# ResolverBoard.net
KiCad netlist of a schematic drawn in EAGLE
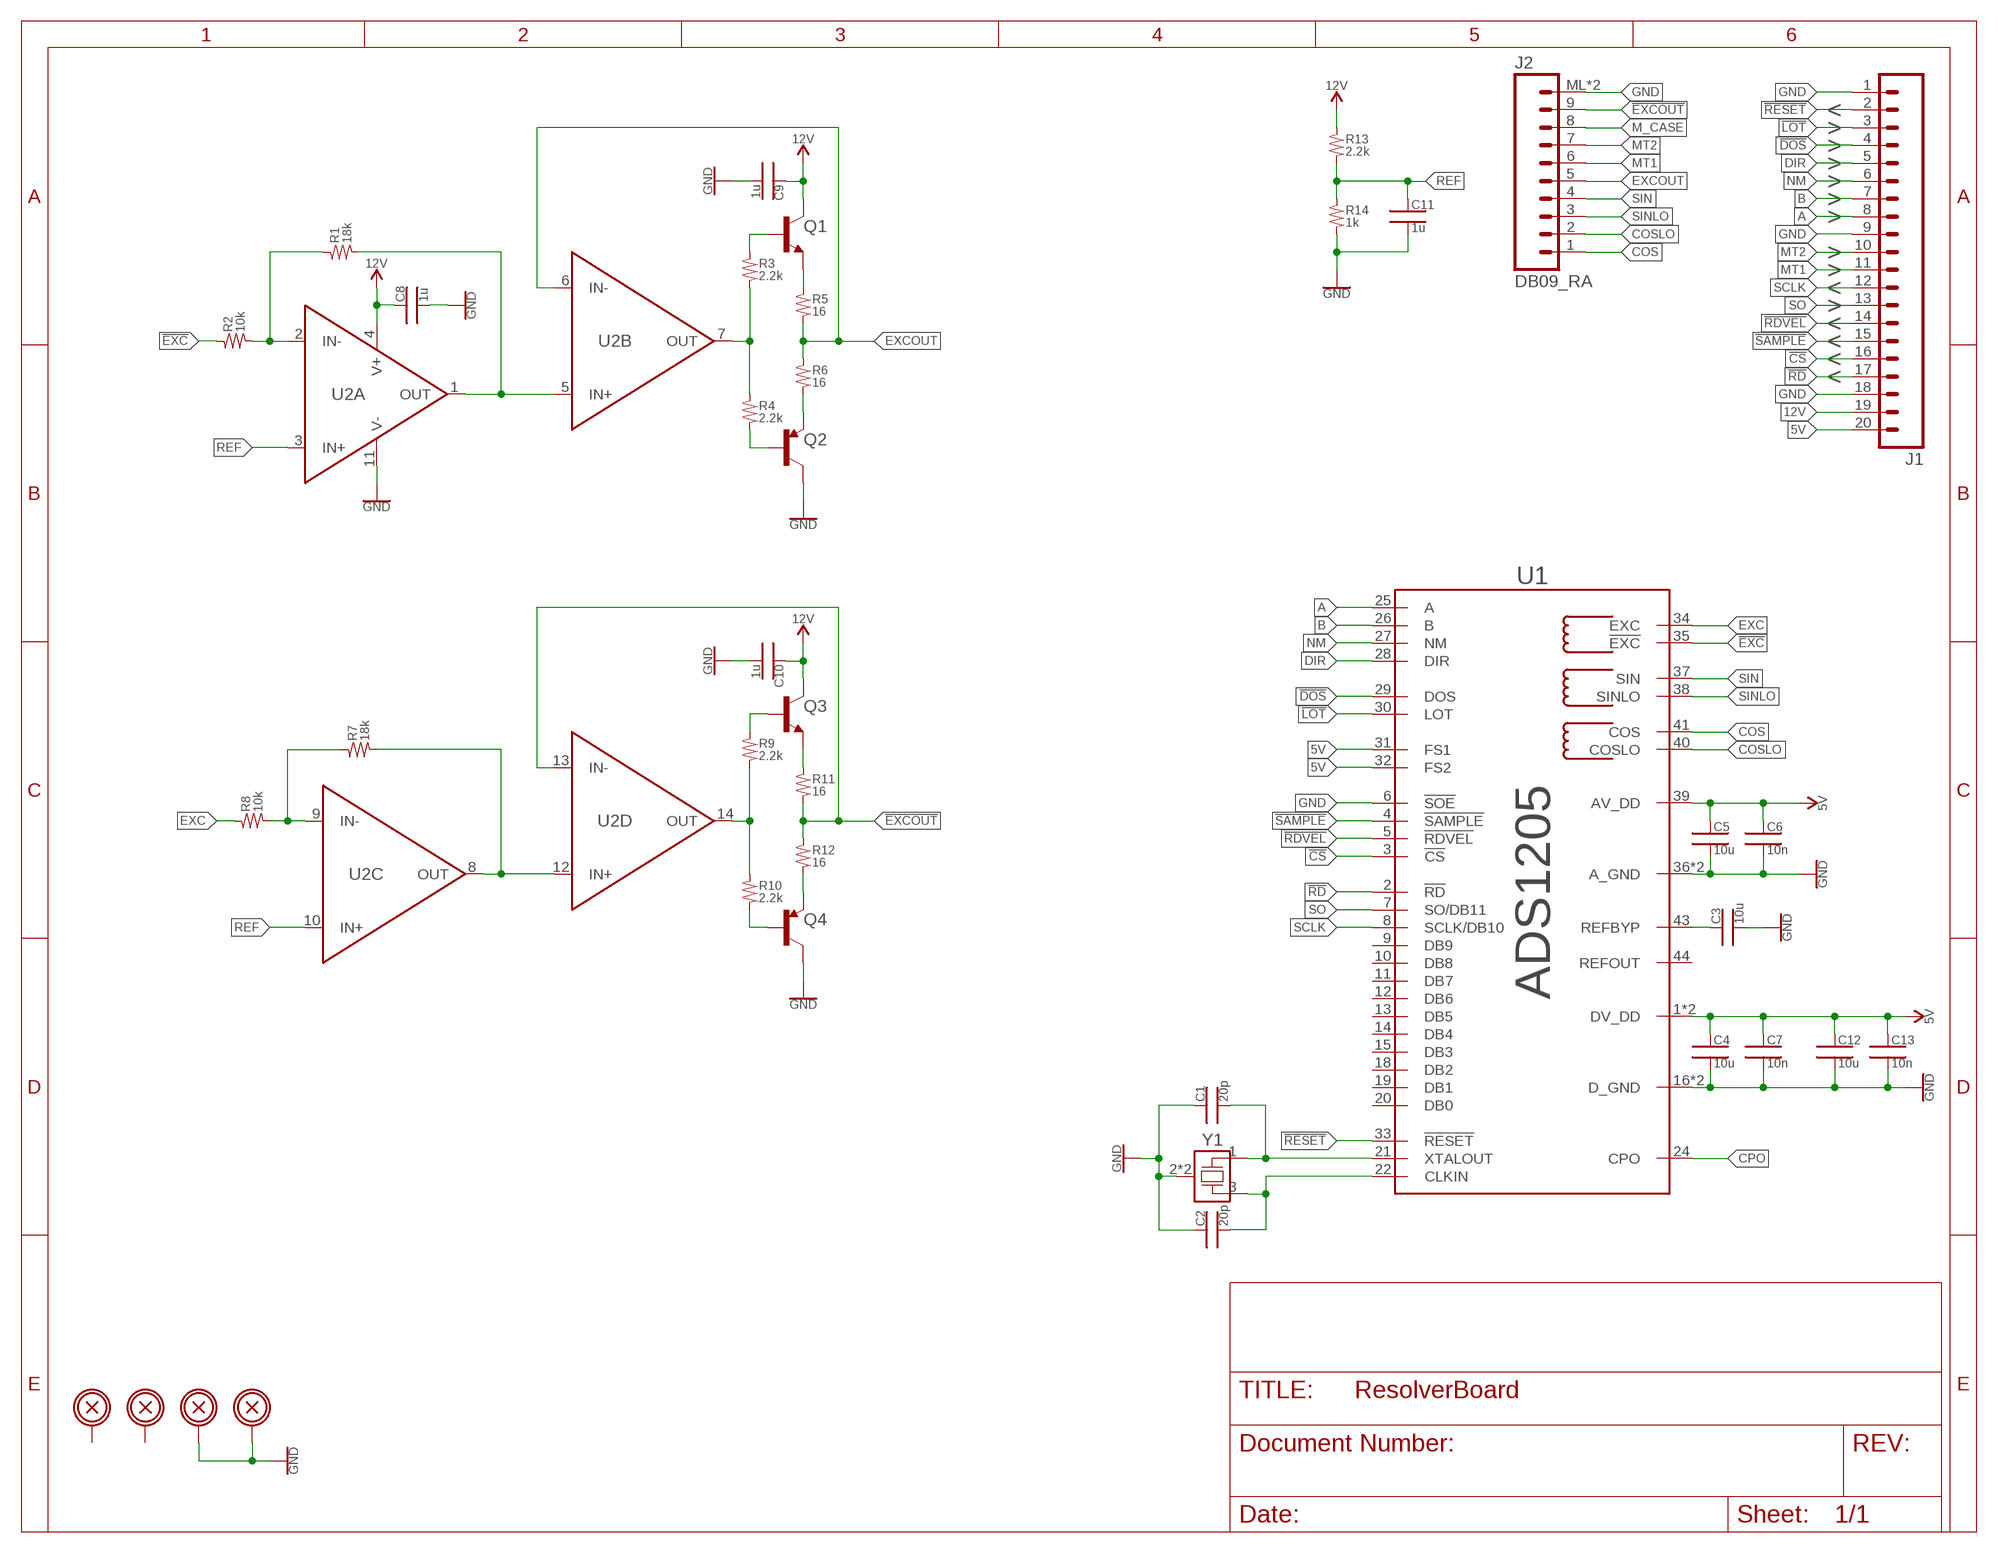
[diagram p0: schematic, sheet 1]

(export (version "E")
  (design (tool "Eeschema 10.0.6"))
  (components
    (comp (ref "C1")
      (value "20p")
      (footprint "eagle-import:0402")
      (libsource (lib "eagle-import") (part "CAP_SMD_0402"))
    )
    (comp (ref "C2")
      (value "20p")
      (footprint "eagle-import:0402")
      (libsource (lib "eagle-import") (part "CAP_SMD_0402"))
    )
    (comp (ref "C3")
      (value "10u")
      (footprint "eagle-import:0603")
      (libsource (lib "eagle-import") (part "CAP_SMD_0603"))
    )
    (comp (ref "C4")
      (value "10u")
      (footprint "eagle-import:0603")
      (libsource (lib "eagle-import") (part "CAP_SMD_0603"))
    )
    (comp (ref "C5")
      (value "10u")
      (footprint "eagle-import:0603")
      (libsource (lib "eagle-import") (part "CAP_SMD_0603"))
    )
    (comp (ref "C6")
      (value "10n")
      (footprint "eagle-import:0402")
      (libsource (lib "eagle-import") (part "CAP_SMD_0402"))
    )
    (comp (ref "C7")
      (value "10n")
      (footprint "eagle-import:0402")
      (libsource (lib "eagle-import") (part "CAP_SMD_0402"))
    )
    (comp (ref "C8")
      (value "1u")
      (footprint "eagle-import:0402")
      (libsource (lib "eagle-import") (part "CAP_SMD_0402"))
    )
    (comp (ref "C9")
      (value "1u")
      (footprint "eagle-import:0402")
      (libsource (lib "eagle-import") (part "CAP_SMD_0402"))
    )
    (comp (ref "C10")
      (value "1u")
      (footprint "eagle-import:0402")
      (libsource (lib "eagle-import") (part "CAP_SMD_0402"))
    )
    (comp (ref "C11")
      (value "1u")
      (footprint "eagle-import:0402")
      (libsource (lib "eagle-import") (part "CAP_SMD_0402"))
    )
    (comp (ref "C12")
      (value "10u")
      (footprint "eagle-import:0603")
      (libsource (lib "eagle-import") (part "CAP_SMD_0603"))
    )
    (comp (ref "C13")
      (value "10n")
      (footprint "eagle-import:0402")
      (libsource (lib "eagle-import") (part "CAP_SMD_0402"))
    )
    (comp (ref "H1")
      (value "BOLTHOLE_M3")
      (footprint "eagle-import:M3_HOLE")
      (libsource (lib "eagle-import") (part "BOLTHOLE_M3"))
    )
    (comp (ref "H2")
      (value "BOLTHOLE_M3")
      (footprint "eagle-import:M3_HOLE")
      (libsource (lib "eagle-import") (part "BOLTHOLE_M3"))
    )
    (comp (ref "H3")
      (value "BOLTHOLE_M3")
      (footprint "eagle-import:M3_HOLE")
      (libsource (lib "eagle-import") (part "BOLTHOLE_M3"))
    )
    (comp (ref "H4")
      (value "BOLTHOLE_M3")
      (footprint "eagle-import:M3_HOLE")
      (libsource (lib "eagle-import") (part "BOLTHOLE_M3"))
    )
    (comp (ref "J1")
      (value "M20")
      (footprint "eagle-import:1X20")
      (libsource (lib "eagle-import") (part "M20"))
    )
    (comp (ref "J2")
      (value "DB09_RA")
      (footprint "eagle-import:AE10921")
      (libsource (lib "eagle-import") (part "DB09_RA"))
    )
    (comp (ref "Q1")
      (value "BJT_NPN")
      (footprint "eagle-import:SOT23-3")
      (libsource (lib "eagle-import") (part "BJT_NPN"))
    )
    (comp (ref "Q2")
      (value "BJT_PNP")
      (footprint "eagle-import:SOT23-3")
      (libsource (lib "eagle-import") (part "BJT_PNP"))
    )
    (comp (ref "Q3")
      (value "BJT_NPN")
      (footprint "eagle-import:SOT23-3")
      (libsource (lib "eagle-import") (part "BJT_NPN"))
    )
    (comp (ref "Q4")
      (value "BJT_PNP")
      (footprint "eagle-import:SOT23-3")
      (libsource (lib "eagle-import") (part "BJT_PNP"))
    )
    (comp (ref "R1")
      (value "18k")
      (footprint "eagle-import:0402")
      (libsource (lib "eagle-import") (part "RES_SMD_0402"))
    )
    (comp (ref "R2")
      (value "10k")
      (footprint "eagle-import:0402")
      (libsource (lib "eagle-import") (part "RES_SMD_0402"))
    )
    (comp (ref "R3")
      (value "2.2k")
      (footprint "eagle-import:0402")
      (libsource (lib "eagle-import") (part "RES_SMD_0402"))
    )
    (comp (ref "R4")
      (value "2.2k")
      (footprint "eagle-import:0402")
      (libsource (lib "eagle-import") (part "RES_SMD_0402"))
    )
    (comp (ref "R5")
      (value "16")
      (footprint "eagle-import:0805")
      (libsource (lib "eagle-import") (part "RES_SMD_0805"))
    )
    (comp (ref "R6")
      (value "16")
      (footprint "eagle-import:0805")
      (libsource (lib "eagle-import") (part "RES_SMD_0805"))
    )
    (comp (ref "R7")
      (value "18k")
      (footprint "eagle-import:0402")
      (libsource (lib "eagle-import") (part "RES_SMD_0402"))
    )
    (comp (ref "R8")
      (value "10k")
      (footprint "eagle-import:0402")
      (libsource (lib "eagle-import") (part "RES_SMD_0402"))
    )
    (comp (ref "R9")
      (value "2.2k")
      (footprint "eagle-import:0402")
      (libsource (lib "eagle-import") (part "RES_SMD_0402"))
    )
    (comp (ref "R10")
      (value "2.2k")
      (footprint "eagle-import:0402")
      (libsource (lib "eagle-import") (part "RES_SMD_0402"))
    )
    (comp (ref "R11")
      (value "16")
      (footprint "eagle-import:0805")
      (libsource (lib "eagle-import") (part "RES_SMD_0805"))
    )
    (comp (ref "R12")
      (value "16")
      (footprint "eagle-import:0805")
      (libsource (lib "eagle-import") (part "RES_SMD_0805"))
    )
    (comp (ref "R13")
      (value "2.2k")
      (footprint "eagle-import:0402")
      (libsource (lib "eagle-import") (part "RES_SMD_0402"))
    )
    (comp (ref "R14")
      (value "1k")
      (footprint "eagle-import:0402")
      (libsource (lib "eagle-import") (part "RES_SMD_0402"))
    )
    (comp (ref "U1")
      (value "ADS1205")
      (footprint "eagle-import:LQFP44")
      (libsource (lib "eagle-import") (part "ADS1205"))
    )
    (comp (ref "U2")
      (value "OPA4171D")
      (footprint "eagle-import:SOIC_14")
      (libsource (lib "eagle-import") (part "OPA4171D"))
    )
    (comp (ref "Y1")
      (value "LFXTAL061486")
      (footprint "eagle-import:5X3.2MM_SMD_XTAL")
      (libsource (lib "eagle-import") (part "LFXTAL061486"))
    )
  )
  (nets
    (net (code "1") (name "/~{CS}") (class "Default")
      (node (ref "J1") (pin "16") (pinfunction "16_16") (pintype "passive"))
      (node (ref "U1") (pin "3") (pinfunction "~{CS}_3") (pintype "bidirectional"))
    )
    (net (code "2") (name "/~{DOS}") (class "Default")
      (node (ref "J1") (pin "4") (pinfunction "4_4") (pintype "passive"))
      (node (ref "U1") (pin "29") (pinfunction "DOS_29") (pintype "bidirectional"))
    )
    (net (code "3") (name "/~{EXCOUT}") (class "Default")
      (node (ref "J2") (pin "9") (pinfunction "9_9") (pintype "passive"))
      (node (ref "R11") (pin "2") (pinfunction "2_2") (pintype "passive"))
      (node (ref "R12") (pin "1") (pinfunction "1_1") (pintype "passive"))
      (node (ref "U2") (pin "13") (pinfunction "IN-_13") (pintype "bidirectional"))
    )
    (net (code "4") (name "/~{EXC}") (class "Default")
      (node (ref "R2") (pin "1") (pinfunction "1_1") (pintype "passive"))
      (node (ref "U1") (pin "35") (pinfunction "~{EXC}_35") (pintype "bidirectional"))
    )
    (net (code "5") (name "/~{LOT}") (class "Default")
      (node (ref "J1") (pin "3") (pinfunction "3_3") (pintype "passive"))
      (node (ref "U1") (pin "30") (pinfunction "LOT_30") (pintype "bidirectional"))
    )
    (net (code "6") (name "/~{RDVEL}") (class "Default")
      (node (ref "J1") (pin "14") (pinfunction "14_14") (pintype "passive"))
      (node (ref "U1") (pin "5") (pinfunction "~{RDVEL}_5") (pintype "bidirectional"))
    )
    (net (code "7") (name "/~{RD}") (class "Default")
      (node (ref "J1") (pin "17") (pinfunction "17_17") (pintype "passive"))
      (node (ref "U1") (pin "2") (pinfunction "~{RD}_2") (pintype "bidirectional"))
    )
    (net (code "8") (name "/~{RESET}") (class "Default")
      (node (ref "J1") (pin "2") (pinfunction "2_2") (pintype "passive"))
      (node (ref "U1") (pin "33") (pinfunction "~{RESET}_33") (pintype "bidirectional"))
    )
    (net (code "9") (name "/~{SAMPLE}") (class "Default")
      (node (ref "J1") (pin "15") (pinfunction "15_15") (pintype "passive"))
      (node (ref "U1") (pin "4") (pinfunction "~{SAMPLE}_4") (pintype "bidirectional"))
    )
    (net (code "10") (name "5V") (class "Default")
      (node (ref "C12") (pin "1") (pinfunction "1_1") (pintype "passive"))
      (node (ref "C13") (pin "1") (pinfunction "1_1") (pintype "passive"))
      (node (ref "C4") (pin "1") (pinfunction "1_1") (pintype "passive"))
      (node (ref "C5") (pin "1") (pinfunction "1_1") (pintype "passive"))
      (node (ref "C6") (pin "1") (pinfunction "1_1") (pintype "passive"))
      (node (ref "C7") (pin "1") (pinfunction "1_1") (pintype "passive"))
      (node (ref "J1") (pin "20") (pinfunction "20_20") (pintype "passive"))
      (node (ref "U1") (pin "1") (pinfunction "DV_DD_1") (pintype "bidirectional"))
      (node (ref "U1") (pin "17") (pinfunction "DV_DD_17") (pintype "bidirectional"))
      (node (ref "U1") (pin "31") (pinfunction "FS1_31") (pintype "bidirectional"))
      (node (ref "U1") (pin "32") (pinfunction "FS2_32") (pintype "bidirectional"))
      (node (ref "U1") (pin "39") (pinfunction "AV_DD_39") (pintype "bidirectional"))
    )
    (net (code "11") (name "12V") (class "Default")
      (node (ref "C10") (pin "1") (pinfunction "1_1") (pintype "passive"))
      (node (ref "C8") (pin "1") (pinfunction "1_1") (pintype "passive"))
      (node (ref "C9") (pin "1") (pinfunction "1_1") (pintype "passive"))
      (node (ref "J1") (pin "19") (pinfunction "19_19") (pintype "passive"))
      (node (ref "Q1") (pin "3") (pinfunction "C_3") (pintype "passive"))
      (node (ref "Q3") (pin "3") (pinfunction "C_3") (pintype "passive"))
      (node (ref "R13") (pin "1") (pinfunction "1_1") (pintype "passive"))
      (node (ref "U2") (pin "4") (pinfunction "V+_4") (pintype "bidirectional"))
    )
    (net (code "12") (name "A") (class "Default")
      (node (ref "J1") (pin "8") (pinfunction "8_8") (pintype "passive"))
      (node (ref "U1") (pin "25") (pinfunction "A_25") (pintype "bidirectional"))
    )
    (net (code "13") (name "B") (class "Default")
      (node (ref "J1") (pin "7") (pinfunction "7_7") (pintype "passive"))
      (node (ref "U1") (pin "26") (pinfunction "B_26") (pintype "bidirectional"))
    )
    (net (code "14") (name "COS") (class "Default")
      (node (ref "J2") (pin "1") (pinfunction "1_1") (pintype "passive"))
      (node (ref "U1") (pin "41") (pinfunction "COS_41") (pintype "bidirectional"))
    )
    (net (code "15") (name "COSLO") (class "Default")
      (node (ref "J2") (pin "2") (pinfunction "2_2") (pintype "passive"))
      (node (ref "U1") (pin "40") (pinfunction "COSLO_40") (pintype "bidirectional"))
    )
    (net (code "16") (name "CPO") (class "Default")
      (node (ref "U1") (pin "24") (pinfunction "CPO_24") (pintype "bidirectional"))
    )
    (net (code "17") (name "DIR") (class "Default")
      (node (ref "J1") (pin "5") (pinfunction "5_5") (pintype "passive"))
      (node (ref "U1") (pin "28") (pinfunction "DIR_28") (pintype "bidirectional"))
    )
    (net (code "18") (name "EXC") (class "Default")
      (node (ref "R8") (pin "1") (pinfunction "1_1") (pintype "passive"))
      (node (ref "U1") (pin "34") (pinfunction "EXC_34") (pintype "bidirectional"))
    )
    (net (code "19") (name "EXCOUT") (class "Default")
      (node (ref "J2") (pin "5") (pinfunction "5_5") (pintype "passive"))
      (node (ref "R5") (pin "2") (pinfunction "2_2") (pintype "passive"))
      (node (ref "R6") (pin "1") (pinfunction "1_1") (pintype "passive"))
      (node (ref "U2") (pin "6") (pinfunction "IN-_6") (pintype "bidirectional"))
    )
    (net (code "20") (name "GND") (class "Default")
      (node (ref "C1") (pin "1") (pinfunction "1_1") (pintype "passive"))
      (node (ref "C10") (pin "2") (pinfunction "2_2") (pintype "passive"))
      (node (ref "C11") (pin "2") (pinfunction "2_2") (pintype "passive"))
      (node (ref "C12") (pin "2") (pinfunction "2_2") (pintype "passive"))
      (node (ref "C13") (pin "2") (pinfunction "2_2") (pintype "passive"))
      (node (ref "C2") (pin "1") (pinfunction "1_1") (pintype "passive"))
      (node (ref "C3") (pin "2") (pinfunction "2_2") (pintype "passive"))
      (node (ref "C4") (pin "2") (pinfunction "2_2") (pintype "passive"))
      (node (ref "C5") (pin "2") (pinfunction "2_2") (pintype "passive"))
      (node (ref "C6") (pin "2") (pinfunction "2_2") (pintype "passive"))
      (node (ref "C7") (pin "2") (pinfunction "2_2") (pintype "passive"))
      (node (ref "C8") (pin "2") (pinfunction "2_2") (pintype "passive"))
      (node (ref "C9") (pin "2") (pinfunction "2_2") (pintype "passive"))
      (node (ref "H3") (pin "P") (pinfunction "P_P") (pintype "bidirectional"))
      (node (ref "H4") (pin "P") (pinfunction "P_P") (pintype "bidirectional"))
      (node (ref "J1") (pin "1") (pinfunction "1_1") (pintype "passive"))
      (node (ref "J1") (pin "18") (pinfunction "18_18") (pintype "passive"))
      (node (ref "J1") (pin "9") (pinfunction "9_9") (pintype "passive"))
      (node (ref "J2") (pin "ML") (pinfunction "10_ML") (pintype "passive"))
      (node (ref "J2") (pin "MR") (pinfunction "10_MR") (pintype "passive"))
      (node (ref "Q2") (pin "3") (pinfunction "C_3") (pintype "passive"))
      (node (ref "Q4") (pin "3") (pinfunction "C_3") (pintype "passive"))
      (node (ref "R14") (pin "2") (pinfunction "2_2") (pintype "passive"))
      (node (ref "U1") (pin "16") (pinfunction "D_GND_16") (pintype "bidirectional"))
      (node (ref "U1") (pin "23") (pinfunction "D_GND_23") (pintype "bidirectional"))
      (node (ref "U1") (pin "36") (pinfunction "A_GND_36") (pintype "bidirectional"))
      (node (ref "U1") (pin "42") (pinfunction "A_GND_42") (pintype "bidirectional"))
      (node (ref "U1") (pin "6") (pinfunction "~{SOE}_6") (pintype "bidirectional"))
      (node (ref "U2") (pin "11") (pinfunction "V-_11") (pintype "bidirectional"))
      (node (ref "Y1") (pin "2") (pinfunction "CASE_2") (pintype "bidirectional"))
      (node (ref "Y1") (pin "4") (pinfunction "CASE_4") (pintype "bidirectional"))
    )
    (net (code "21") (name "MT1") (class "Default")
      (node (ref "J1") (pin "11") (pinfunction "11_11") (pintype "passive"))
      (node (ref "J2") (pin "6") (pinfunction "6_6") (pintype "passive"))
    )
    (net (code "22") (name "MT2") (class "Default")
      (node (ref "J1") (pin "10") (pinfunction "10_10") (pintype "passive"))
      (node (ref "J2") (pin "7") (pinfunction "7_7") (pintype "passive"))
    )
    (net (code "23") (name "M_CASE") (class "Default")
      (node (ref "J2") (pin "8") (pinfunction "8_8") (pintype "passive"))
    )
    (net (code "24") (name "NM") (class "Default")
      (node (ref "J1") (pin "6") (pinfunction "6_6") (pintype "passive"))
      (node (ref "U1") (pin "27") (pinfunction "NM_27") (pintype "bidirectional"))
    )
    (net (code "25") (name "Net-(Q1-B)") (class "Default")
      (node (ref "Q1") (pin "1") (pinfunction "B_1") (pintype "passive"))
      (node (ref "R3") (pin "1") (pinfunction "1_1") (pintype "passive"))
    )
    (net (code "26") (name "Net-(Q1-E)") (class "Default")
      (node (ref "Q1") (pin "2") (pinfunction "E_2") (pintype "passive"))
      (node (ref "R5") (pin "1") (pinfunction "1_1") (pintype "passive"))
    )
    (net (code "27") (name "Net-(Q2-B)") (class "Default")
      (node (ref "Q2") (pin "1") (pinfunction "B_1") (pintype "passive"))
      (node (ref "R4") (pin "2") (pinfunction "2_2") (pintype "passive"))
    )
    (net (code "28") (name "Net-(Q2-E)") (class "Default")
      (node (ref "Q2") (pin "2") (pinfunction "E_2") (pintype "passive"))
      (node (ref "R6") (pin "2") (pinfunction "2_2") (pintype "passive"))
    )
    (net (code "29") (name "Net-(Q3-B)") (class "Default")
      (node (ref "Q3") (pin "1") (pinfunction "B_1") (pintype "passive"))
      (node (ref "R9") (pin "1") (pinfunction "1_1") (pintype "passive"))
    )
    (net (code "30") (name "Net-(Q3-E)") (class "Default")
      (node (ref "Q3") (pin "2") (pinfunction "E_2") (pintype "passive"))
      (node (ref "R11") (pin "1") (pinfunction "1_1") (pintype "passive"))
    )
    (net (code "31") (name "Net-(Q4-B)") (class "Default")
      (node (ref "Q4") (pin "1") (pinfunction "B_1") (pintype "passive"))
      (node (ref "R10") (pin "2") (pinfunction "2_2") (pintype "passive"))
    )
    (net (code "32") (name "Net-(Q4-E)") (class "Default")
      (node (ref "Q4") (pin "2") (pinfunction "E_2") (pintype "passive"))
      (node (ref "R12") (pin "2") (pinfunction "2_2") (pintype "passive"))
    )
    (net (code "33") (name "Net-(U1-CLKIN)") (class "Default")
      (node (ref "C2") (pin "2") (pinfunction "2_2") (pintype "passive"))
      (node (ref "U1") (pin "22") (pinfunction "CLKIN_22") (pintype "bidirectional"))
      (node (ref "Y1") (pin "3") (pinfunction "X2_3") (pintype "bidirectional"))
    )
    (net (code "34") (name "Net-(U1-REFBYP)") (class "Default")
      (node (ref "C3") (pin "1") (pinfunction "1_1") (pintype "passive"))
      (node (ref "U1") (pin "43") (pinfunction "REFBYP_43") (pintype "bidirectional"))
    )
    (net (code "35") (name "Net-(U1-XTALOUT)") (class "Default")
      (node (ref "C1") (pin "2") (pinfunction "2_2") (pintype "passive"))
      (node (ref "U1") (pin "21") (pinfunction "XTALOUT_21") (pintype "bidirectional"))
      (node (ref "Y1") (pin "1") (pinfunction "X1_1") (pintype "bidirectional"))
    )
    (net (code "36") (name "Net-(U2A-IN-)") (class "Default")
      (node (ref "R1") (pin "1") (pinfunction "1_1") (pintype "passive"))
      (node (ref "R2") (pin "2") (pinfunction "2_2") (pintype "passive"))
      (node (ref "U2") (pin "2") (pinfunction "IN-_2") (pintype "bidirectional"))
    )
    (net (code "37") (name "Net-(U2A-OUT)") (class "Default")
      (node (ref "R1") (pin "2") (pinfunction "2_2") (pintype "passive"))
      (node (ref "U2") (pin "1") (pinfunction "OUT_1") (pintype "bidirectional"))
      (node (ref "U2") (pin "5") (pinfunction "IN+_5") (pintype "bidirectional"))
    )
    (net (code "38") (name "Net-(U2B-OUT)") (class "Default")
      (node (ref "R3") (pin "2") (pinfunction "2_2") (pintype "passive"))
      (node (ref "R4") (pin "1") (pinfunction "1_1") (pintype "passive"))
      (node (ref "U2") (pin "7") (pinfunction "OUT_7") (pintype "bidirectional"))
    )
    (net (code "39") (name "Net-(U2C-IN-)") (class "Default")
      (node (ref "R7") (pin "1") (pinfunction "1_1") (pintype "passive"))
      (node (ref "R8") (pin "2") (pinfunction "2_2") (pintype "passive"))
      (node (ref "U2") (pin "9") (pinfunction "IN-_9") (pintype "bidirectional"))
    )
    (net (code "40") (name "Net-(U2C-OUT)") (class "Default")
      (node (ref "R7") (pin "2") (pinfunction "2_2") (pintype "passive"))
      (node (ref "U2") (pin "12") (pinfunction "IN+_12") (pintype "bidirectional"))
      (node (ref "U2") (pin "8") (pinfunction "OUT_8") (pintype "bidirectional"))
    )
    (net (code "41") (name "Net-(U2D-OUT)") (class "Default")
      (node (ref "R10") (pin "1") (pinfunction "1_1") (pintype "passive"))
      (node (ref "R9") (pin "2") (pinfunction "2_2") (pintype "passive"))
      (node (ref "U2") (pin "14") (pinfunction "OUT_14") (pintype "bidirectional"))
    )
    (net (code "42") (name "REF") (class "Default")
      (node (ref "C11") (pin "1") (pinfunction "1_1") (pintype "passive"))
      (node (ref "R13") (pin "2") (pinfunction "2_2") (pintype "passive"))
      (node (ref "R14") (pin "1") (pinfunction "1_1") (pintype "passive"))
      (node (ref "U2") (pin "10") (pinfunction "IN+_10") (pintype "bidirectional"))
      (node (ref "U2") (pin "3") (pinfunction "IN+_3") (pintype "bidirectional"))
    )
    (net (code "43") (name "SCLK") (class "Default")
      (node (ref "J1") (pin "12") (pinfunction "12_12") (pintype "passive"))
      (node (ref "U1") (pin "8") (pinfunction "SCLK/DB10_8") (pintype "bidirectional"))
    )
    (net (code "44") (name "SIN") (class "Default")
      (node (ref "J2") (pin "4") (pinfunction "4_4") (pintype "passive"))
      (node (ref "U1") (pin "37") (pinfunction "SIN_37") (pintype "bidirectional"))
    )
    (net (code "45") (name "SINLO") (class "Default")
      (node (ref "J2") (pin "3") (pinfunction "3_3") (pintype "passive"))
      (node (ref "U1") (pin "38") (pinfunction "SINLO_38") (pintype "bidirectional"))
    )
    (net (code "46") (name "SO") (class "Default")
      (node (ref "J1") (pin "13") (pinfunction "13_13") (pintype "passive"))
      (node (ref "U1") (pin "7") (pinfunction "SO/DB11_7") (pintype "bidirectional"))
    )
    (net (code "47") (name "unconnected-(H1-PadP)") (class "Default")
      (node (ref "H1") (pin "P") (pinfunction "P_P") (pintype "bidirectional"))
    )
    (net (code "48") (name "unconnected-(H2-PadP)") (class "Default")
      (node (ref "H2") (pin "P") (pinfunction "P_P") (pintype "bidirectional"))
    )
    (net (code "49") (name "unconnected-(U1-DB0-Pad20)") (class "Default")
      (node (ref "U1") (pin "20") (pinfunction "DB0_20") (pintype "bidirectional"))
    )
    (net (code "50") (name "unconnected-(U1-DB1-Pad19)") (class "Default")
      (node (ref "U1") (pin "19") (pinfunction "DB1_19") (pintype "bidirectional"))
    )
    (net (code "51") (name "unconnected-(U1-DB2-Pad18)") (class "Default")
      (node (ref "U1") (pin "18") (pinfunction "DB2_18") (pintype "bidirectional"))
    )
    (net (code "52") (name "unconnected-(U1-DB3-Pad15)") (class "Default")
      (node (ref "U1") (pin "15") (pinfunction "DB3_15") (pintype "bidirectional"))
    )
    (net (code "53") (name "unconnected-(U1-DB4-Pad14)") (class "Default")
      (node (ref "U1") (pin "14") (pinfunction "DB4_14") (pintype "bidirectional"))
    )
    (net (code "54") (name "unconnected-(U1-DB5-Pad13)") (class "Default")
      (node (ref "U1") (pin "13") (pinfunction "DB5_13") (pintype "bidirectional"))
    )
    (net (code "55") (name "unconnected-(U1-DB6-Pad12)") (class "Default")
      (node (ref "U1") (pin "12") (pinfunction "DB6_12") (pintype "bidirectional"))
    )
    (net (code "56") (name "unconnected-(U1-DB7-Pad11)") (class "Default")
      (node (ref "U1") (pin "11") (pinfunction "DB7_11") (pintype "bidirectional"))
    )
    (net (code "57") (name "unconnected-(U1-DB8-Pad10)") (class "Default")
      (node (ref "U1") (pin "10") (pinfunction "DB8_10") (pintype "bidirectional"))
    )
    (net (code "58") (name "unconnected-(U1-DB9-Pad9)") (class "Default")
      (node (ref "U1") (pin "9") (pinfunction "DB9_9") (pintype "bidirectional"))
    )
    (net (code "59") (name "unconnected-(U1-REFOUT-Pad44)") (class "Default")
      (node (ref "U1") (pin "44") (pinfunction "REFOUT_44") (pintype "bidirectional"))
    )
  )
)
